# 1-PF0100_PMIC.net
KiCad netlist of a schematic drawn in Altium Designer
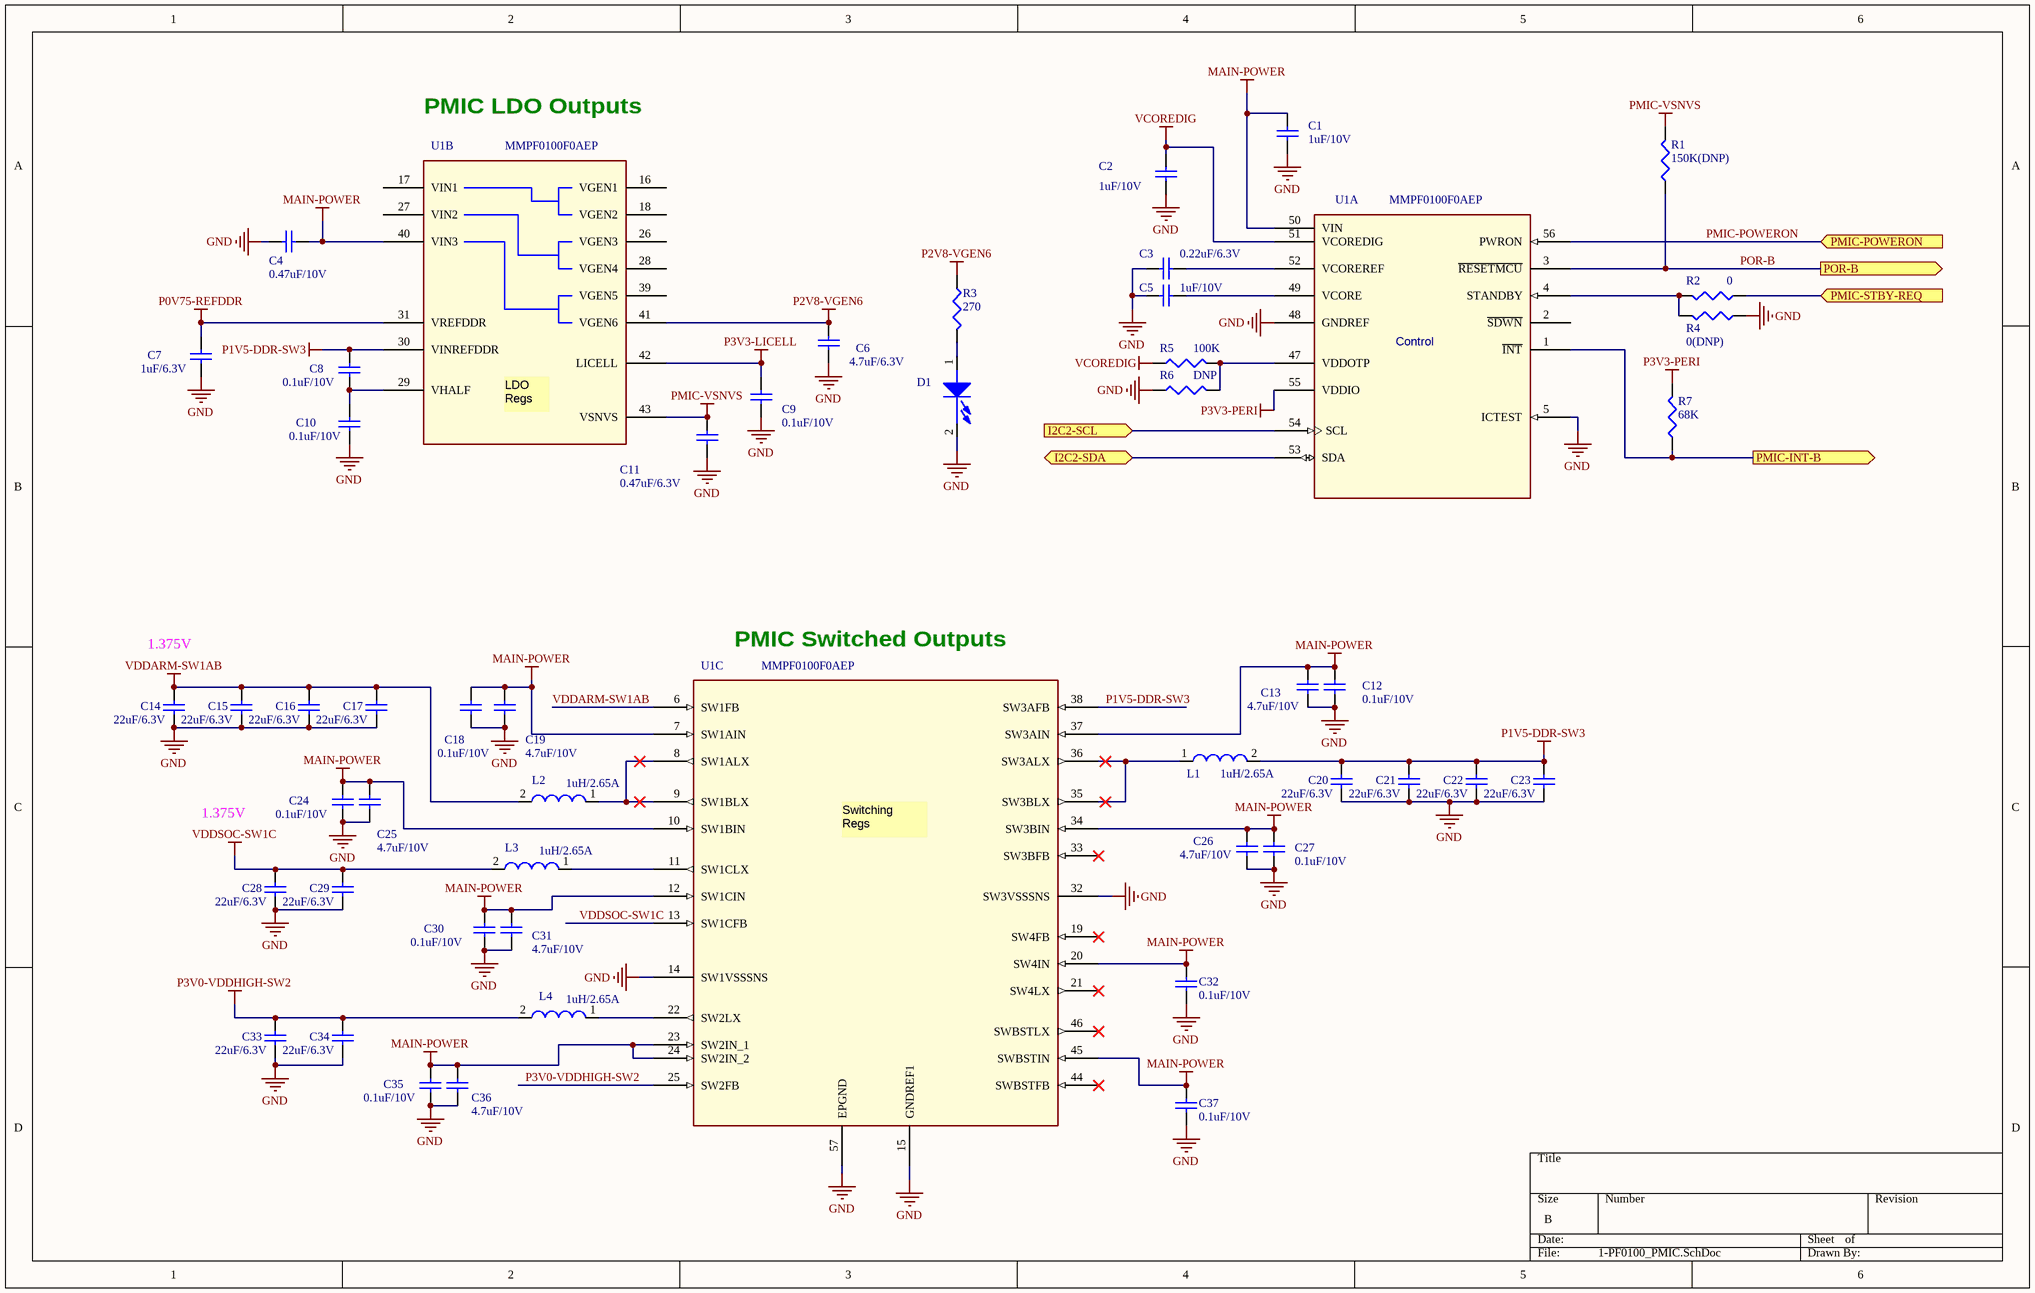
[diagram p0: 1-PF0100_PMIC.SchDoc]

(export (version "E")
  (design (tool "Eeschema 10.0.6"))
  (components
    (comp (ref "C1")
      (value "1uF/10V")
      (footprint "0603_CC")
      (description "Capacitor")
      (fields (field (name "PUBLISHER") "Altium Limited"))
      (libsource (lib "Miscellaneous Devices") (part "Cap"))
    )
    (comp (ref "C2")
      (value "1uF/10V")
      (footprint "0603_CC")
      (description "Capacitor")
      (fields (field (name "PUBLISHER") "Altium Limited"))
      (libsource (lib "Miscellaneous Devices") (part "Cap"))
    )
    (comp (ref "C3")
      (value "0.22uF/6.3V")
      (footprint "0402_CC")
      (description "Capacitor")
      (fields (field (name "PUBLISHER") "Altium Limited"))
      (libsource (lib "Miscellaneous Devices") (part "Cap"))
    )
    (comp (ref "C4")
      (value "0.47uF/10V")
      (footprint "0603_CC")
      (description "Capacitor")
      (fields (field (name "PUBLISHER") "Altium Limited"))
      (libsource (lib "Miscellaneous Devices") (part "Cap"))
    )
    (comp (ref "C5")
      (value "1uF/10V")
      (footprint "0603_CC")
      (description "Capacitor")
      (fields (field (name "PUBLISHER") "Altium Limited"))
      (libsource (lib "Miscellaneous Devices") (part "Cap"))
    )
    (comp (ref "C6")
      (value "4.7uF/6.3V")
      (footprint "0603_CC")
      (description "Capacitor")
      (fields (field (name "PUBLISHER") "Altium Limited"))
      (libsource (lib "Miscellaneous Devices") (part "Cap"))
    )
    (comp (ref "C7")
      (value "1uF/6.3V")
      (footprint "0603_CC")
      (description "Capacitor")
      (fields (field (name "PUBLISHER") "Altium Limited"))
      (libsource (lib "Miscellaneous Devices") (part "Cap"))
    )
    (comp (ref "C8")
      (value "0.1uF/10V")
      (footprint "0402_CC")
      (description "Capacitor")
      (fields (field (name "PUBLISHER") "Altium Limited"))
      (libsource (lib "Miscellaneous Devices") (part "Cap"))
    )
    (comp (ref "C9")
      (value "0.1uF/10V")
      (footprint "0402_CC")
      (description "Capacitor")
      (fields (field (name "PUBLISHER") "Altium Limited"))
      (libsource (lib "Miscellaneous Devices") (part "Cap"))
    )
    (comp (ref "C10")
      (value "0.1uF/10V")
      (footprint "0402_CC")
      (description "Capacitor")
      (fields (field (name "PUBLISHER") "Altium Limited"))
      (libsource (lib "Miscellaneous Devices") (part "Cap"))
    )
    (comp (ref "C11")
      (value "0.47uF/6.3V")
      (footprint "0402_CC")
      (description "Capacitor")
      (fields (field (name "PUBLISHER") "Altium Limited"))
      (libsource (lib "Miscellaneous Devices") (part "Cap"))
    )
    (comp (ref "C12")
      (value "0.1uF/10V")
      (footprint "0402_CC")
      (description "Capacitor")
      (fields (field (name "PUBLISHER") "Altium Limited"))
      (libsource (lib "Miscellaneous Devices") (part "Cap"))
    )
    (comp (ref "C13")
      (value "4.7uF/10V")
      (footprint "0805_CC")
      (description "Capacitor")
      (fields (field (name "PUBLISHER") "Altium Limited"))
      (libsource (lib "Miscellaneous Devices") (part "Cap"))
    )
    (comp (ref "C14")
      (value "22uF/6.3V")
      (footprint "0805_CC")
      (description "Capacitor")
      (fields (field (name "PUBLISHER") "Altium Limited"))
      (libsource (lib "Miscellaneous Devices") (part "Cap"))
    )
    (comp (ref "C15")
      (value "22uF/6.3V")
      (footprint "0805_CC")
      (description "Capacitor")
      (fields (field (name "PUBLISHER") "Altium Limited"))
      (libsource (lib "Miscellaneous Devices") (part "Cap"))
    )
    (comp (ref "C16")
      (value "22uF/6.3V")
      (footprint "0805_CC")
      (description "Capacitor")
      (fields (field (name "PUBLISHER") "Altium Limited"))
      (libsource (lib "Miscellaneous Devices") (part "Cap"))
    )
    (comp (ref "C17")
      (value "22uF/6.3V")
      (footprint "0805_CC")
      (description "Capacitor")
      (fields (field (name "PUBLISHER") "Altium Limited"))
      (libsource (lib "Miscellaneous Devices") (part "Cap"))
    )
    (comp (ref "C18")
      (value "0.1uF/10V")
      (footprint "0402_CC")
      (description "Capacitor")
      (fields (field (name "PUBLISHER") "Altium Limited"))
      (libsource (lib "Miscellaneous Devices") (part "Cap"))
    )
    (comp (ref "C19")
      (value "4.7uF/10V")
      (footprint "0805_CC")
      (description "Capacitor")
      (fields (field (name "PUBLISHER") "Altium Limited"))
      (libsource (lib "Miscellaneous Devices") (part "Cap"))
    )
    (comp (ref "C20")
      (value "22uF/6.3V")
      (footprint "0805_CC")
      (description "Capacitor")
      (fields (field (name "PUBLISHER") "Altium Limited"))
      (libsource (lib "Miscellaneous Devices") (part "Cap"))
    )
    (comp (ref "C21")
      (value "22uF/6.3V")
      (footprint "0805_CC")
      (description "Capacitor")
      (fields (field (name "PUBLISHER") "Altium Limited"))
      (libsource (lib "Miscellaneous Devices") (part "Cap"))
    )
    (comp (ref "C22")
      (value "22uF/6.3V")
      (footprint "0805_CC")
      (description "Capacitor")
      (fields (field (name "PUBLISHER") "Altium Limited"))
      (libsource (lib "Miscellaneous Devices") (part "Cap"))
    )
    (comp (ref "C23")
      (value "22uF/6.3V")
      (footprint "0805_CC")
      (description "Capacitor")
      (fields (field (name "PUBLISHER") "Altium Limited"))
      (libsource (lib "Miscellaneous Devices") (part "Cap"))
    )
    (comp (ref "C24")
      (value "0.1uF/10V")
      (footprint "0402_CC")
      (description "Capacitor")
      (fields (field (name "PUBLISHER") "Altium Limited"))
      (libsource (lib "Miscellaneous Devices") (part "Cap"))
    )
    (comp (ref "C25")
      (value "4.7uF/10V")
      (footprint "0805_CC")
      (description "Capacitor")
      (fields (field (name "PUBLISHER") "Altium Limited"))
      (libsource (lib "Miscellaneous Devices") (part "Cap"))
    )
    (comp (ref "C26")
      (value "4.7uF/10V")
      (footprint "0805_CC")
      (description "Capacitor")
      (fields (field (name "PUBLISHER") "Altium Limited"))
      (libsource (lib "Miscellaneous Devices") (part "Cap"))
    )
    (comp (ref "C27")
      (value "0.1uF/10V")
      (footprint "0402_CC")
      (description "Capacitor")
      (fields (field (name "PUBLISHER") "Altium Limited"))
      (libsource (lib "Miscellaneous Devices") (part "Cap"))
    )
    (comp (ref "C28")
      (value "22uF/6.3V")
      (footprint "0805_CC")
      (description "Capacitor")
      (fields (field (name "PUBLISHER") "Altium Limited"))
      (libsource (lib "Miscellaneous Devices") (part "Cap"))
    )
    (comp (ref "C29")
      (value "22uF/6.3V")
      (footprint "0805_CC")
      (description "Capacitor")
      (fields (field (name "PUBLISHER") "Altium Limited"))
      (libsource (lib "Miscellaneous Devices") (part "Cap"))
    )
    (comp (ref "C30")
      (value "0.1uF/10V")
      (footprint "0402_CC")
      (description "Capacitor")
      (fields (field (name "PUBLISHER") "Altium Limited"))
      (libsource (lib "Miscellaneous Devices") (part "Cap"))
    )
    (comp (ref "C31")
      (value "4.7uF/10V")
      (footprint "0805_CC")
      (description "Capacitor")
      (fields (field (name "PUBLISHER") "Altium Limited"))
      (libsource (lib "Miscellaneous Devices") (part "Cap"))
    )
    (comp (ref "C32")
      (value "0.1uF/10V")
      (footprint "0402_CC")
      (description "Capacitor")
      (fields (field (name "PUBLISHER") "Altium Limited"))
      (libsource (lib "Miscellaneous Devices") (part "Cap"))
    )
    (comp (ref "C33")
      (value "22uF/6.3V")
      (footprint "0805_CC")
      (description "Capacitor")
      (fields (field (name "PUBLISHER") "Altium Limited"))
      (libsource (lib "Miscellaneous Devices") (part "Cap"))
    )
    (comp (ref "C34")
      (value "22uF/6.3V")
      (footprint "0805_CC")
      (description "Capacitor")
      (fields (field (name "PUBLISHER") "Altium Limited"))
      (libsource (lib "Miscellaneous Devices") (part "Cap"))
    )
    (comp (ref "C35")
      (value "0.1uF/10V")
      (footprint "0402_CC")
      (description "Capacitor")
      (fields (field (name "PUBLISHER") "Altium Limited"))
      (libsource (lib "Miscellaneous Devices") (part "Cap"))
    )
    (comp (ref "C36")
      (value "4.7uF/10V")
      (footprint "0805_CC")
      (description "Capacitor")
      (fields (field (name "PUBLISHER") "Altium Limited"))
      (libsource (lib "Miscellaneous Devices") (part "Cap"))
    )
    (comp (ref "C37")
      (value "0.1uF/10V")
      (footprint "0402_CC")
      (description "Capacitor")
      (fields (field (name "PUBLISHER") "Altium Limited"))
      (libsource (lib "Miscellaneous Devices") (part "Cap"))
    )
    (comp (ref "D1") (value "LED GREEN") (footprint "LED0603") (libsource (lib "*") (part "LN01401_1")))
    (comp (ref "L1")
      (value "1uH/2.65A")
      (footprint "IND-1uH-2.65A")
      (description "IND PWR 1UH@100KHZ 2.65A 20% SMT")
      (fields (field (name "TOLERANCE") "20%"))
      (libsource (lib "") (part "INDUCTOR_1"))
    )
    (comp (ref "L2")
      (value "1uH/2.65A")
      (footprint "IND-1uH-2.65A")
      (description "IND PWR 1UH@100KHZ 2.65A 20% SMT")
      (fields (field (name "TOLERANCE") "20%"))
      (libsource (lib "*") (part "INDUCTOR"))
    )
    (comp (ref "L3")
      (value "1uH/2.65A")
      (footprint "IND-1uH-2.65A")
      (description "IND PWR 1UH@1MHZ 2A 30% SMT")
      (fields (field (name "TOLERANCE") "30%"))
      (libsource (lib "*") (part "INDUCTOR"))
    )
    (comp (ref "L4")
      (value "1uH/2.65A")
      (footprint "IND-1uH-2.65A")
      (description "IND PWR 1UH@1MHZ 2A 30% SMT")
      (fields (field (name "TOLERANCE") "30%"))
      (libsource (lib "*") (part "INDUCTOR"))
    )
    (comp (ref "R1")
      (value "150K(DNP)")
      (footprint "0402_CC")
      (description "Resistor")
      (fields (field (name "PUBLISHER") "Altium Limited"))
      (libsource (lib "Miscellaneous Devices") (part "Res3"))
    )
    (comp (ref "R2")
      (value "0")
      (footprint "0402_CC")
      (description "Resistor")
      (fields (field (name "PUBLISHER") "Altium Limited"))
      (libsource (lib "Miscellaneous Devices") (part "Res3"))
    )
    (comp (ref "R3")
      (value "270")
      (footprint "0402_CC")
      (description "Resistor")
      (fields (field (name "PUBLISHER") "Altium Limited"))
      (libsource (lib "Miscellaneous Devices") (part "Res3"))
    )
    (comp (ref "R4")
      (value "0(DNP)")
      (footprint "0402_CC")
      (description "Resistor")
      (fields (field (name "PUBLISHER") "Altium Limited"))
      (libsource (lib "Miscellaneous Devices") (part "Res3"))
    )
    (comp (ref "R5")
      (value "100K")
      (footprint "0402_CC")
      (description "Resistor")
      (fields (field (name "PUBLISHER") "Altium Limited"))
      (libsource (lib "Miscellaneous Devices") (part "Res3"))
    )
    (comp (ref "R6")
      (value "DNP")
      (footprint "0402_CC")
      (description "Resistor")
      (fields (field (name "PUBLISHER") "Altium Limited"))
      (libsource (lib "Miscellaneous Devices") (part "Res3"))
    )
    (comp (ref "R7")
      (value "68K")
      (footprint "0402_CC")
      (description "Resistor")
      (fields (field (name "PUBLISHER") "Altium Limited"))
      (libsource (lib "Miscellaneous Devices") (part "Res3"))
    )
    (comp (ref "U1")
      (value "MMPF0100F0ZES")
      (footprint "QFN-56")
      (description "IC POWER MANAGEMENT 2.8-4.5V QFN56")
      (libsource (lib "*") (part "MMPF0100NPZES_56P"))
    )
  )
  (nets
    (net (code "1") (name "/I2C2-SCL") (class "Default")
      (node (ref "U1") (pin "54") (pinfunction "SCL_54") (pintype "input"))
    )
    (net (code "2") (name "/I2C2-SDA") (class "Default")
      (node (ref "U1") (pin "53") (pinfunction "SDA_53") (pintype "bidirectional"))
    )
    (net (code "3") (name "/PMIC-INT-B") (class "Default")
      (node (ref "R7") (pin "1") (pinfunction "1_1") (pintype "passive"))
      (node (ref "U1") (pin "1") (pinfunction "~{INT}_1") (pintype "open_collector"))
    )
    (net (code "4") (name "/PMIC-POWERON") (class "Default")
      (node (ref "U1") (pin "56") (pinfunction "PWRON_56") (pintype "input"))
    )
    (net (code "5") (name "/PMIC-STBY-REQ") (class "Default")
      (node (ref "R2") (pin "1") (pinfunction "1_1") (pintype "passive"))
    )
    (net (code "6") (name "/POR-B") (class "Default")
      (node (ref "R1") (pin "1") (pinfunction "1_1") (pintype "passive"))
      (node (ref "U1") (pin "3") (pinfunction "~{RESETMCU}_3") (pintype "open_collector"))
    )
    (net (code "7") (name "GND") (class "Default")
      (node (ref "C1") (pin "2") (pinfunction "2_2") (pintype "passive"))
      (node (ref "C10") (pin "2") (pinfunction "2_2") (pintype "passive"))
      (node (ref "C11") (pin "2") (pinfunction "2_2") (pintype "passive"))
      (node (ref "C12") (pin "2") (pinfunction "2_2") (pintype "passive"))
      (node (ref "C13") (pin "2") (pinfunction "2_2") (pintype "passive"))
      (node (ref "C14") (pin "2") (pinfunction "2_2") (pintype "passive"))
      (node (ref "C15") (pin "2") (pinfunction "2_2") (pintype "passive"))
      (node (ref "C16") (pin "2") (pinfunction "2_2") (pintype "passive"))
      (node (ref "C17") (pin "2") (pinfunction "2_2") (pintype "passive"))
      (node (ref "C18") (pin "2") (pinfunction "2_2") (pintype "passive"))
      (node (ref "C19") (pin "2") (pinfunction "2_2") (pintype "passive"))
      (node (ref "C2") (pin "2") (pinfunction "2_2") (pintype "passive"))
      (node (ref "C20") (pin "2") (pinfunction "2_2") (pintype "passive"))
      (node (ref "C21") (pin "2") (pinfunction "2_2") (pintype "passive"))
      (node (ref "C22") (pin "2") (pinfunction "2_2") (pintype "passive"))
      (node (ref "C23") (pin "2") (pinfunction "2_2") (pintype "passive"))
      (node (ref "C24") (pin "2") (pinfunction "2_2") (pintype "passive"))
      (node (ref "C25") (pin "2") (pinfunction "2_2") (pintype "passive"))
      (node (ref "C26") (pin "2") (pinfunction "2_2") (pintype "passive"))
      (node (ref "C27") (pin "2") (pinfunction "2_2") (pintype "passive"))
      (node (ref "C28") (pin "2") (pinfunction "2_2") (pintype "passive"))
      (node (ref "C29") (pin "2") (pinfunction "2_2") (pintype "passive"))
      (node (ref "C3") (pin "2") (pinfunction "2_2") (pintype "passive"))
      (node (ref "C30") (pin "2") (pinfunction "2_2") (pintype "passive"))
      (node (ref "C31") (pin "2") (pinfunction "2_2") (pintype "passive"))
      (node (ref "C32") (pin "2") (pinfunction "2_2") (pintype "passive"))
      (node (ref "C33") (pin "2") (pinfunction "2_2") (pintype "passive"))
      (node (ref "C34") (pin "2") (pinfunction "2_2") (pintype "passive"))
      (node (ref "C35") (pin "2") (pinfunction "2_2") (pintype "passive"))
      (node (ref "C36") (pin "2") (pinfunction "2_2") (pintype "passive"))
      (node (ref "C37") (pin "1") (pinfunction "1_1") (pintype "passive"))
      (node (ref "C4") (pin "2") (pinfunction "2_2") (pintype "passive"))
      (node (ref "C5") (pin "2") (pinfunction "2_2") (pintype "passive"))
      (node (ref "C6") (pin "2") (pinfunction "2_2") (pintype "passive"))
      (node (ref "C7") (pin "2") (pinfunction "2_2") (pintype "passive"))
      (node (ref "C9") (pin "2") (pinfunction "2_2") (pintype "passive"))
      (node (ref "D1") (pin "2") (pinfunction "CATHODE_2") (pintype "passive"))
      (node (ref "R4") (pin "1") (pinfunction "1_1") (pintype "passive"))
      (node (ref "R6") (pin "1") (pinfunction "1_1") (pintype "passive"))
      (node (ref "U1") (pin "14") (pinfunction "SW1VSSSNS_14") (pintype "power_in"))
      (node (ref "U1") (pin "15") (pinfunction "GNDREF1_15") (pintype "power_in"))
      (node (ref "U1") (pin "32") (pinfunction "SW3VSSSNS_32") (pintype "power_in"))
      (node (ref "U1") (pin "48") (pinfunction "GNDREF_48") (pintype "power_in"))
      (node (ref "U1") (pin "5") (pinfunction "ICTEST_5") (pintype "input"))
      (node (ref "U1") (pin "57") (pinfunction "EPGND_57") (pintype "power_in"))
    )
    (net (code "8") (name "MAIN-POWER") (class "Default")
      (node (ref "C1") (pin "1") (pinfunction "1_1") (pintype "passive"))
      (node (ref "C12") (pin "1") (pinfunction "1_1") (pintype "passive"))
      (node (ref "C13") (pin "1") (pinfunction "1_1") (pintype "passive"))
      (node (ref "C18") (pin "1") (pinfunction "1_1") (pintype "passive"))
      (node (ref "C19") (pin "1") (pinfunction "1_1") (pintype "passive"))
      (node (ref "C24") (pin "1") (pinfunction "1_1") (pintype "passive"))
      (node (ref "C25") (pin "1") (pinfunction "1_1") (pintype "passive"))
      (node (ref "C26") (pin "1") (pinfunction "1_1") (pintype "passive"))
      (node (ref "C27") (pin "1") (pinfunction "1_1") (pintype "passive"))
      (node (ref "C30") (pin "1") (pinfunction "1_1") (pintype "passive"))
      (node (ref "C31") (pin "1") (pinfunction "1_1") (pintype "passive"))
      (node (ref "C32") (pin "1") (pinfunction "1_1") (pintype "passive"))
      (node (ref "C35") (pin "1") (pinfunction "1_1") (pintype "passive"))
      (node (ref "C36") (pin "1") (pinfunction "1_1") (pintype "passive"))
      (node (ref "C37") (pin "2") (pinfunction "2_2") (pintype "passive"))
      (node (ref "C4") (pin "1") (pinfunction "1_1") (pintype "passive"))
      (node (ref "U1") (pin "10") (pinfunction "SW1BIN_10") (pintype "input"))
      (node (ref "U1") (pin "12") (pinfunction "SW1CIN_12") (pintype "input"))
      (node (ref "U1") (pin "20") (pinfunction "SW4IN_20") (pintype "input"))
      (node (ref "U1") (pin "23") (pinfunction "SW2IN_1_23") (pintype "input"))
      (node (ref "U1") (pin "24") (pinfunction "SW2IN_2_24") (pintype "input"))
      (node (ref "U1") (pin "34") (pinfunction "SW3BIN_34") (pintype "input"))
      (node (ref "U1") (pin "37") (pinfunction "SW3AIN_37") (pintype "input"))
      (node (ref "U1") (pin "40") (pinfunction "VIN3_40") (pintype "power_in"))
      (node (ref "U1") (pin "45") (pinfunction "SWBSTIN_45") (pintype "input"))
      (node (ref "U1") (pin "50") (pinfunction "VIN_50") (pintype "power_in"))
      (node (ref "U1") (pin "7") (pinfunction "SW1AIN_7") (pintype "input"))
    )
    (net (code "9") (name "Net-(D1-ANODE)") (class "Default")
      (node (ref "D1") (pin "1") (pinfunction "ANODE_1") (pintype "passive"))
      (node (ref "R3") (pin "2") (pinfunction "2_2") (pintype "passive"))
    )
    (net (code "10") (name "Net-(U1A-STANDBY)") (class "Default")
      (node (ref "R2") (pin "2") (pinfunction "2_2") (pintype "passive"))
      (node (ref "R4") (pin "2") (pinfunction "2_2") (pintype "passive"))
      (node (ref "U1") (pin "4") (pinfunction "STANDBY_4") (pintype "input"))
    )
    (net (code "11") (name "Net-(U1A-VCORE)") (class "Default")
      (node (ref "C5") (pin "1") (pinfunction "1_1") (pintype "passive"))
      (node (ref "U1") (pin "49") (pinfunction "VCORE_49") (pintype "power_in"))
    )
    (net (code "12") (name "Net-(U1A-VCOREREF)") (class "Default")
      (node (ref "C3") (pin "1") (pinfunction "1_1") (pintype "passive"))
      (node (ref "U1") (pin "52") (pinfunction "VCOREREF_52") (pintype "power_in"))
    )
    (net (code "13") (name "Net-(U1A-VDDOTP)") (class "Default")
      (node (ref "R5") (pin "2") (pinfunction "2_2") (pintype "passive"))
      (node (ref "R6") (pin "2") (pinfunction "2_2") (pintype "passive"))
      (node (ref "U1") (pin "47") (pinfunction "VDDOTP_47") (pintype "power_in"))
    )
    (net (code "14") (name "Net-(U1B-VHALF)") (class "Default")
      (node (ref "C10") (pin "1") (pinfunction "1_1") (pintype "passive"))
      (node (ref "C8") (pin "2") (pinfunction "2_2") (pintype "passive"))
      (node (ref "U1") (pin "29") (pinfunction "VHALF_29") (pintype "power_in"))
    )
    (net (code "15") (name "Net-(U1C-SW1ALX)") (class "Default")
      (node (ref "L2") (pin "1") (pinfunction "1_1") (pintype "passive"))
      (node (ref "U1") (pin "8") (pinfunction "SW1ALX_8") (pintype "output"))
      (node (ref "U1") (pin "9") (pinfunction "SW1BLX_9") (pintype "output"))
    )
    (net (code "16") (name "Net-(U1C-SW1CLX)") (class "Default")
      (node (ref "L3") (pin "1") (pinfunction "1_1") (pintype "passive"))
      (node (ref "U1") (pin "11") (pinfunction "SW1CLX_11") (pintype "output"))
    )
    (net (code "17") (name "Net-(U1C-SW2LX)") (class "Default")
      (node (ref "L4") (pin "1") (pinfunction "1_1") (pintype "passive"))
      (node (ref "U1") (pin "22") (pinfunction "SW2LX_22") (pintype "output"))
    )
    (net (code "18") (name "Net-(U1C-SW3ALX)") (class "Default")
      (node (ref "L1") (pin "1") (pinfunction "1_1") (pintype "passive"))
      (node (ref "U1") (pin "35") (pinfunction "SW3BLX_35") (pintype "output"))
      (node (ref "U1") (pin "36") (pinfunction "SW3ALX_36") (pintype "output"))
    )
    (net (code "19") (name "P0V75-REFDDR") (class "Default")
      (node (ref "C7") (pin "1") (pinfunction "1_1") (pintype "passive"))
      (node (ref "U1") (pin "31") (pinfunction "VREFDDR_31") (pintype "power_in"))
    )
    (net (code "20") (name "P1V5-DDR-SW3") (class "Default")
      (node (ref "C20") (pin "1") (pinfunction "1_1") (pintype "passive"))
      (node (ref "C21") (pin "1") (pinfunction "1_1") (pintype "passive"))
      (node (ref "C22") (pin "1") (pinfunction "1_1") (pintype "passive"))
      (node (ref "C23") (pin "1") (pinfunction "1_1") (pintype "passive"))
      (node (ref "C8") (pin "1") (pinfunction "1_1") (pintype "passive"))
      (node (ref "L1") (pin "2") (pinfunction "2_2") (pintype "passive"))
      (node (ref "U1") (pin "30") (pinfunction "VINREFDDR_30") (pintype "power_in"))
      (node (ref "U1") (pin "38") (pinfunction "SW3AFB_38") (pintype "input"))
    )
    (net (code "21") (name "P2V8-VGEN6") (class "Default")
      (node (ref "C6") (pin "1") (pinfunction "1_1") (pintype "passive"))
      (node (ref "R3") (pin "1") (pinfunction "1_1") (pintype "passive"))
      (node (ref "U1") (pin "41") (pinfunction "VGEN6_41") (pintype "power_in"))
    )
    (net (code "22") (name "P3V0-VDDHIGH-SW2") (class "Default")
      (node (ref "C33") (pin "1") (pinfunction "1_1") (pintype "passive"))
      (node (ref "C34") (pin "1") (pinfunction "1_1") (pintype "passive"))
      (node (ref "L4") (pin "2") (pinfunction "2_2") (pintype "passive"))
      (node (ref "U1") (pin "25") (pinfunction "SW2FB_25") (pintype "input"))
    )
    (net (code "23") (name "P3V3-LICELL") (class "Default")
      (node (ref "C9") (pin "1") (pinfunction "1_1") (pintype "passive"))
      (node (ref "U1") (pin "42") (pinfunction "LICELL_42") (pintype "power_in"))
    )
    (net (code "24") (name "P3V3-PERI") (class "Default")
      (node (ref "R7") (pin "2") (pinfunction "2_2") (pintype "passive"))
      (node (ref "U1") (pin "55") (pinfunction "VDDIO_55") (pintype "power_in"))
    )
    (net (code "25") (name "PMIC-VSNVS") (class "Default")
      (node (ref "C11") (pin "1") (pinfunction "1_1") (pintype "passive"))
      (node (ref "R1") (pin "2") (pinfunction "2_2") (pintype "passive"))
      (node (ref "U1") (pin "43") (pinfunction "VSNVS_43") (pintype "power_in"))
    )
    (net (code "26") (name "VCOREDIG") (class "Default")
      (node (ref "C2") (pin "1") (pinfunction "1_1") (pintype "passive"))
      (node (ref "R5") (pin "1") (pinfunction "1_1") (pintype "passive"))
      (node (ref "U1") (pin "51") (pinfunction "VCOREDIG_51") (pintype "power_in"))
    )
    (net (code "27") (name "VDDARM-SW1AB") (class "Default")
      (node (ref "C14") (pin "1") (pinfunction "1_1") (pintype "passive"))
      (node (ref "C15") (pin "1") (pinfunction "1_1") (pintype "passive"))
      (node (ref "C16") (pin "1") (pinfunction "1_1") (pintype "passive"))
      (node (ref "C17") (pin "1") (pinfunction "1_1") (pintype "passive"))
      (node (ref "L2") (pin "2") (pinfunction "2_2") (pintype "passive"))
      (node (ref "U1") (pin "6") (pinfunction "SW1FB_6") (pintype "input"))
    )
    (net (code "28") (name "VDDSOC-SW1C") (class "Default")
      (node (ref "C28") (pin "1") (pinfunction "1_1") (pintype "passive"))
      (node (ref "C29") (pin "1") (pinfunction "1_1") (pintype "passive"))
      (node (ref "L3") (pin "2") (pinfunction "2_2") (pintype "passive"))
      (node (ref "U1") (pin "13") (pinfunction "SW1CFB_13") (pintype "input"))
    )
    (net (code "29") (name "unconnected-(U1A-~{SDWN}-Pad2)") (class "Default")
      (node (ref "U1") (pin "2") (pinfunction "~{SDWN}_2") (pintype "open_collector"))
    )
    (net (code "30") (name "unconnected-(U1B-VGEN1-Pad16)") (class "Default")
      (node (ref "U1") (pin "16") (pinfunction "VGEN1_16") (pintype "power_in"))
    )
    (net (code "31") (name "unconnected-(U1B-VGEN2-Pad18)") (class "Default")
      (node (ref "U1") (pin "18") (pinfunction "VGEN2_18") (pintype "power_in"))
    )
    (net (code "32") (name "unconnected-(U1B-VGEN3-Pad26)") (class "Default")
      (node (ref "U1") (pin "26") (pinfunction "VGEN3_26") (pintype "power_in"))
    )
    (net (code "33") (name "unconnected-(U1B-VGEN4-Pad28)") (class "Default")
      (node (ref "U1") (pin "28") (pinfunction "VGEN4_28") (pintype "power_in"))
    )
    (net (code "34") (name "unconnected-(U1B-VGEN5-Pad39)") (class "Default")
      (node (ref "U1") (pin "39") (pinfunction "VGEN5_39") (pintype "power_in"))
    )
    (net (code "35") (name "unconnected-(U1B-VIN1-Pad17)") (class "Default")
      (node (ref "U1") (pin "17") (pinfunction "VIN1_17") (pintype "power_in"))
    )
    (net (code "36") (name "unconnected-(U1B-VIN2-Pad27)") (class "Default")
      (node (ref "U1") (pin "27") (pinfunction "VIN2_27") (pintype "power_in"))
    )
    (net (code "37") (name "unconnected-(U1C-SW3BFB-Pad33)") (class "Default")
      (node (ref "U1") (pin "33") (pinfunction "SW3BFB_33") (pintype "input+no_connect"))
    )
    (net (code "38") (name "unconnected-(U1C-SW4FB-Pad19)") (class "Default")
      (node (ref "U1") (pin "19") (pinfunction "SW4FB_19") (pintype "input+no_connect"))
    )
    (net (code "39") (name "unconnected-(U1C-SW4LX-Pad21)") (class "Default")
      (node (ref "U1") (pin "21") (pinfunction "SW4LX_21") (pintype "output+no_connect"))
    )
    (net (code "40") (name "unconnected-(U1C-SWBSTFB-Pad44)") (class "Default")
      (node (ref "U1") (pin "44") (pinfunction "SWBSTFB_44") (pintype "input+no_connect"))
    )
    (net (code "41") (name "unconnected-(U1C-SWBSTLX-Pad46)") (class "Default")
      (node (ref "U1") (pin "46") (pinfunction "SWBSTLX_46") (pintype "output+no_connect"))
    )
  )
)
